# ATMEGA8-ATMEGA16.net
KiCad netlist of a schematic drawn in Altium Designer
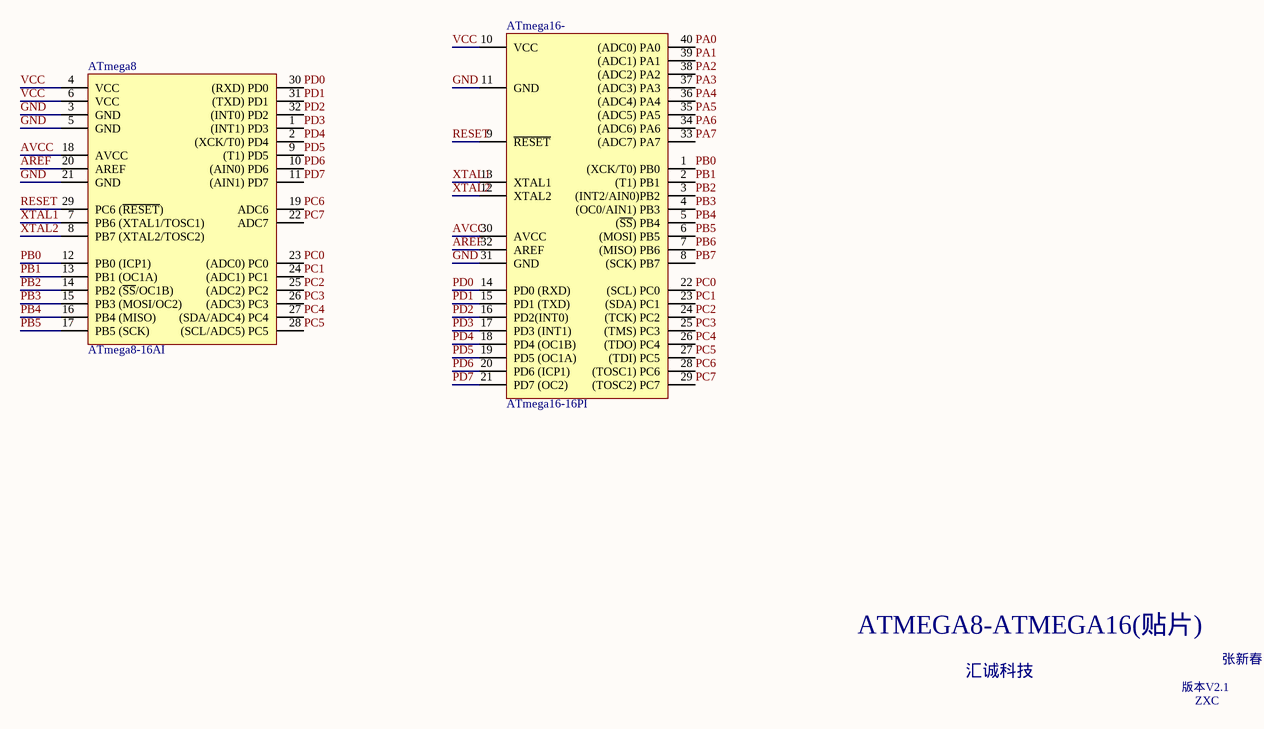
[diagram p0: ATMEGA8-ATMEGA16(贴片).SchDoc]

(export (version "E")
  (design (tool "Eeschema 10.0.6"))
  (components
    (comp (ref "ATmega8")
      (value "ATmega8-16AI")
      (footprint "TQFP-32_0.8/7×7mm")
      (description "8 位微处理器/32引脚")
      (fields (field (name "发布者") "磊元工作室"))
      (libsource (lib "微控制处理器") (part "ATmega8-A"))
    )
    (comp (ref "ATmega16-")
      (value "ATmega16-16PI")
      (footprint "底座DIP-40/引脚15.24mm")
      (description "8 位微处理器/40引脚")
      (fields (field (name "发布者") "磊元工作室"))
      (libsource (lib "微控制处理器") (part "ATmega16-P"))
    )
  )
  (nets
    (net (code "1") (name "/AREF") (class "Default")
      (node (ref "ATmega16-") (pin "32") (pinfunction "AREF_32") (pintype "passive"))
      (node (ref "ATmega8") (pin "20") (pinfunction "AREF_20") (pintype "passive"))
    )
    (net (code "2") (name "/AVCC") (class "Default")
      (node (ref "ATmega16-") (pin "30") (pinfunction "AVCC_30") (pintype "passive"))
      (node (ref "ATmega8") (pin "18") (pinfunction "AVCC_18") (pintype "passive"))
    )
    (net (code "3") (name "/GND") (class "Default")
      (node (ref "ATmega16-") (pin "11") (pinfunction "GND_11") (pintype "passive"))
      (node (ref "ATmega16-") (pin "31") (pinfunction "GND_31") (pintype "passive"))
      (node (ref "ATmega8") (pin "21") (pinfunction "GND_21") (pintype "passive"))
      (node (ref "ATmega8") (pin "3") (pinfunction "GND_3") (pintype "passive"))
      (node (ref "ATmega8") (pin "5") (pinfunction "GND_5") (pintype "passive"))
    )
    (net (code "4") (name "/PA0") (class "Default")
      (node (ref "ATmega16-") (pin "40") (pinfunction "(ADC0)_PA0_40") (pintype "passive"))
    )
    (net (code "5") (name "/PA1") (class "Default")
      (node (ref "ATmega16-") (pin "39") (pinfunction "(ADC1)_PA1_39") (pintype "passive"))
    )
    (net (code "6") (name "/PA2") (class "Default")
      (node (ref "ATmega16-") (pin "38") (pinfunction "(ADC2)_PA2_38") (pintype "passive"))
    )
    (net (code "7") (name "/PA3") (class "Default")
      (node (ref "ATmega16-") (pin "37") (pinfunction "(ADC3)_PA3_37") (pintype "passive"))
    )
    (net (code "8") (name "/PA4") (class "Default")
      (node (ref "ATmega16-") (pin "36") (pinfunction "(ADC4)_PA4_36") (pintype "passive"))
    )
    (net (code "9") (name "/PA5") (class "Default")
      (node (ref "ATmega16-") (pin "35") (pinfunction "(ADC5)_PA5_35") (pintype "passive"))
    )
    (net (code "10") (name "/PA6") (class "Default")
      (node (ref "ATmega16-") (pin "34") (pinfunction "(ADC6)_PA6_34") (pintype "passive"))
    )
    (net (code "11") (name "/PA7") (class "Default")
      (node (ref "ATmega16-") (pin "33") (pinfunction "(ADC7)_PA7_33") (pintype "passive"))
    )
    (net (code "12") (name "/PB0") (class "Default")
      (node (ref "ATmega16-") (pin "1") (pinfunction "(XCK/T0)_PB0_1") (pintype "passive"))
      (node (ref "ATmega8") (pin "12") (pinfunction "PB0_(ICP1)_12") (pintype "passive"))
    )
    (net (code "13") (name "/PB1") (class "Default")
      (node (ref "ATmega16-") (pin "2") (pinfunction "(T1)_PB1_2") (pintype "passive"))
      (node (ref "ATmega8") (pin "13") (pinfunction "PB1_(OC1A)_13") (pintype "passive"))
    )
    (net (code "14") (name "/PB2") (class "Default")
      (node (ref "ATmega16-") (pin "3") (pinfunction "(INT2/AIN0)PB2_3") (pintype "passive"))
      (node (ref "ATmega8") (pin "14") (pinfunction "PB2_(~{SS}/OC1B)_14") (pintype "passive"))
    )
    (net (code "15") (name "/PB3") (class "Default")
      (node (ref "ATmega16-") (pin "4") (pinfunction "(OC0/AIN1)_PB3_4") (pintype "passive"))
      (node (ref "ATmega8") (pin "15") (pinfunction "PB3_(MOSI/OC2)_15") (pintype "passive"))
    )
    (net (code "16") (name "/PB4") (class "Default")
      (node (ref "ATmega16-") (pin "5") (pinfunction "(~{SS})_PB4_5") (pintype "passive"))
      (node (ref "ATmega8") (pin "16") (pinfunction "PB4_(MISO)_16") (pintype "passive"))
    )
    (net (code "17") (name "/PB5") (class "Default")
      (node (ref "ATmega16-") (pin "6") (pinfunction "(MOSI)_PB5_6") (pintype "passive"))
      (node (ref "ATmega8") (pin "17") (pinfunction "PB5_(SCK)_17") (pintype "passive"))
    )
    (net (code "18") (name "/PB6") (class "Default")
      (node (ref "ATmega16-") (pin "7") (pinfunction "(MISO)_PB6_7") (pintype "passive"))
    )
    (net (code "19") (name "/PB7") (class "Default")
      (node (ref "ATmega16-") (pin "8") (pinfunction "(SCK)_PB7_8") (pintype "passive"))
    )
    (net (code "20") (name "/PC0") (class "Default")
      (node (ref "ATmega16-") (pin "22") (pinfunction "(SCL)_PC0_22") (pintype "passive"))
      (node (ref "ATmega8") (pin "23") (pinfunction "(ADC0)_PC0_23") (pintype "passive"))
    )
    (net (code "21") (name "/PC1") (class "Default")
      (node (ref "ATmega16-") (pin "23") (pinfunction "(SDA)_PC1_23") (pintype "passive"))
      (node (ref "ATmega8") (pin "24") (pinfunction "(ADC1)_PC1_24") (pintype "passive"))
    )
    (net (code "22") (name "/PC2") (class "Default")
      (node (ref "ATmega16-") (pin "24") (pinfunction "(TCK)_PC2_24") (pintype "passive"))
      (node (ref "ATmega8") (pin "25") (pinfunction "(ADC2)_PC2_25") (pintype "passive"))
    )
    (net (code "23") (name "/PC3") (class "Default")
      (node (ref "ATmega16-") (pin "25") (pinfunction "(TMS)_PC3_25") (pintype "passive"))
      (node (ref "ATmega8") (pin "26") (pinfunction "(ADC3)_PC3_26") (pintype "passive"))
    )
    (net (code "24") (name "/PC4") (class "Default")
      (node (ref "ATmega16-") (pin "26") (pinfunction "(TDO)_PC4_26") (pintype "passive"))
      (node (ref "ATmega8") (pin "27") (pinfunction "(SDA/ADC4)_PC4_27") (pintype "passive"))
    )
    (net (code "25") (name "/PC5") (class "Default")
      (node (ref "ATmega16-") (pin "27") (pinfunction "(TDI)_PC5_27") (pintype "passive"))
      (node (ref "ATmega8") (pin "28") (pinfunction "(SCL/ADC5)_PC5_28") (pintype "passive"))
    )
    (net (code "26") (name "/PC6") (class "Default")
      (node (ref "ATmega16-") (pin "28") (pinfunction "(TOSC1)_PC6_28") (pintype "passive"))
      (node (ref "ATmega8") (pin "19") (pinfunction "ADC6_19") (pintype "passive"))
    )
    (net (code "27") (name "/PC7") (class "Default")
      (node (ref "ATmega16-") (pin "29") (pinfunction "(TOSC2)_PC7_29") (pintype "passive"))
      (node (ref "ATmega8") (pin "22") (pinfunction "ADC7_22") (pintype "passive"))
    )
    (net (code "28") (name "/PD0") (class "Default")
      (node (ref "ATmega16-") (pin "14") (pinfunction "PD0_(RXD)_14") (pintype "passive"))
      (node (ref "ATmega8") (pin "30") (pinfunction "(RXD)_PD0_30") (pintype "passive"))
    )
    (net (code "29") (name "/PD1") (class "Default")
      (node (ref "ATmega16-") (pin "15") (pinfunction "PD1_(TXD)_15") (pintype "passive"))
      (node (ref "ATmega8") (pin "31") (pinfunction "(TXD)_PD1_31") (pintype "passive"))
    )
    (net (code "30") (name "/PD2") (class "Default")
      (node (ref "ATmega16-") (pin "16") (pinfunction "PD2(INT0)_16") (pintype "passive"))
      (node (ref "ATmega8") (pin "32") (pinfunction "(INT0)_PD2_32") (pintype "passive"))
    )
    (net (code "31") (name "/PD3") (class "Default")
      (node (ref "ATmega16-") (pin "17") (pinfunction "PD3_(INT1)_17") (pintype "passive"))
      (node (ref "ATmega8") (pin "1") (pinfunction "(INT1)_PD3_1") (pintype "passive"))
    )
    (net (code "32") (name "/PD4") (class "Default")
      (node (ref "ATmega16-") (pin "18") (pinfunction "PD4_(OC1B)_18") (pintype "passive"))
      (node (ref "ATmega8") (pin "2") (pinfunction "(XCK/T0)_PD4_2") (pintype "passive"))
    )
    (net (code "33") (name "/PD5") (class "Default")
      (node (ref "ATmega16-") (pin "19") (pinfunction "PD5_(OC1A)_19") (pintype "passive"))
      (node (ref "ATmega8") (pin "9") (pinfunction "(T1)_PD5_9") (pintype "passive"))
    )
    (net (code "34") (name "/PD6") (class "Default")
      (node (ref "ATmega16-") (pin "20") (pinfunction "PD6_(ICP1)_20") (pintype "passive"))
      (node (ref "ATmega8") (pin "10") (pinfunction "(AIN0)_PD6_10") (pintype "passive"))
    )
    (net (code "35") (name "/PD7") (class "Default")
      (node (ref "ATmega16-") (pin "21") (pinfunction "PD7_(OC2)_21") (pintype "passive"))
      (node (ref "ATmega8") (pin "11") (pinfunction "(AIN1)_PD7_11") (pintype "passive"))
    )
    (net (code "36") (name "/RESET") (class "Default")
      (node (ref "ATmega16-") (pin "9") (pinfunction "~{RESET}_9") (pintype "passive"))
      (node (ref "ATmega8") (pin "29") (pinfunction "PC6_(~{RESET})_29") (pintype "passive"))
    )
    (net (code "37") (name "/VCC") (class "Default")
      (node (ref "ATmega16-") (pin "10") (pinfunction "VCC_10") (pintype "passive"))
      (node (ref "ATmega8") (pin "4") (pinfunction "VCC_4") (pintype "passive"))
      (node (ref "ATmega8") (pin "6") (pinfunction "VCC_6") (pintype "passive"))
    )
    (net (code "38") (name "/XTAL1") (class "Default")
      (node (ref "ATmega16-") (pin "13") (pinfunction "XTAL1_13") (pintype "passive"))
      (node (ref "ATmega8") (pin "7") (pinfunction "PB6_(XTAL1/TOSC1)_7") (pintype "passive"))
    )
    (net (code "39") (name "/XTAL2") (class "Default")
      (node (ref "ATmega16-") (pin "12") (pinfunction "XTAL2_12") (pintype "passive"))
      (node (ref "ATmega8") (pin "8") (pinfunction "PB7_(XTAL2/TOSC2)_8") (pintype "passive"))
    )
  )
)
